# Main.net
KiCad netlist of a schematic drawn in Altium Designer
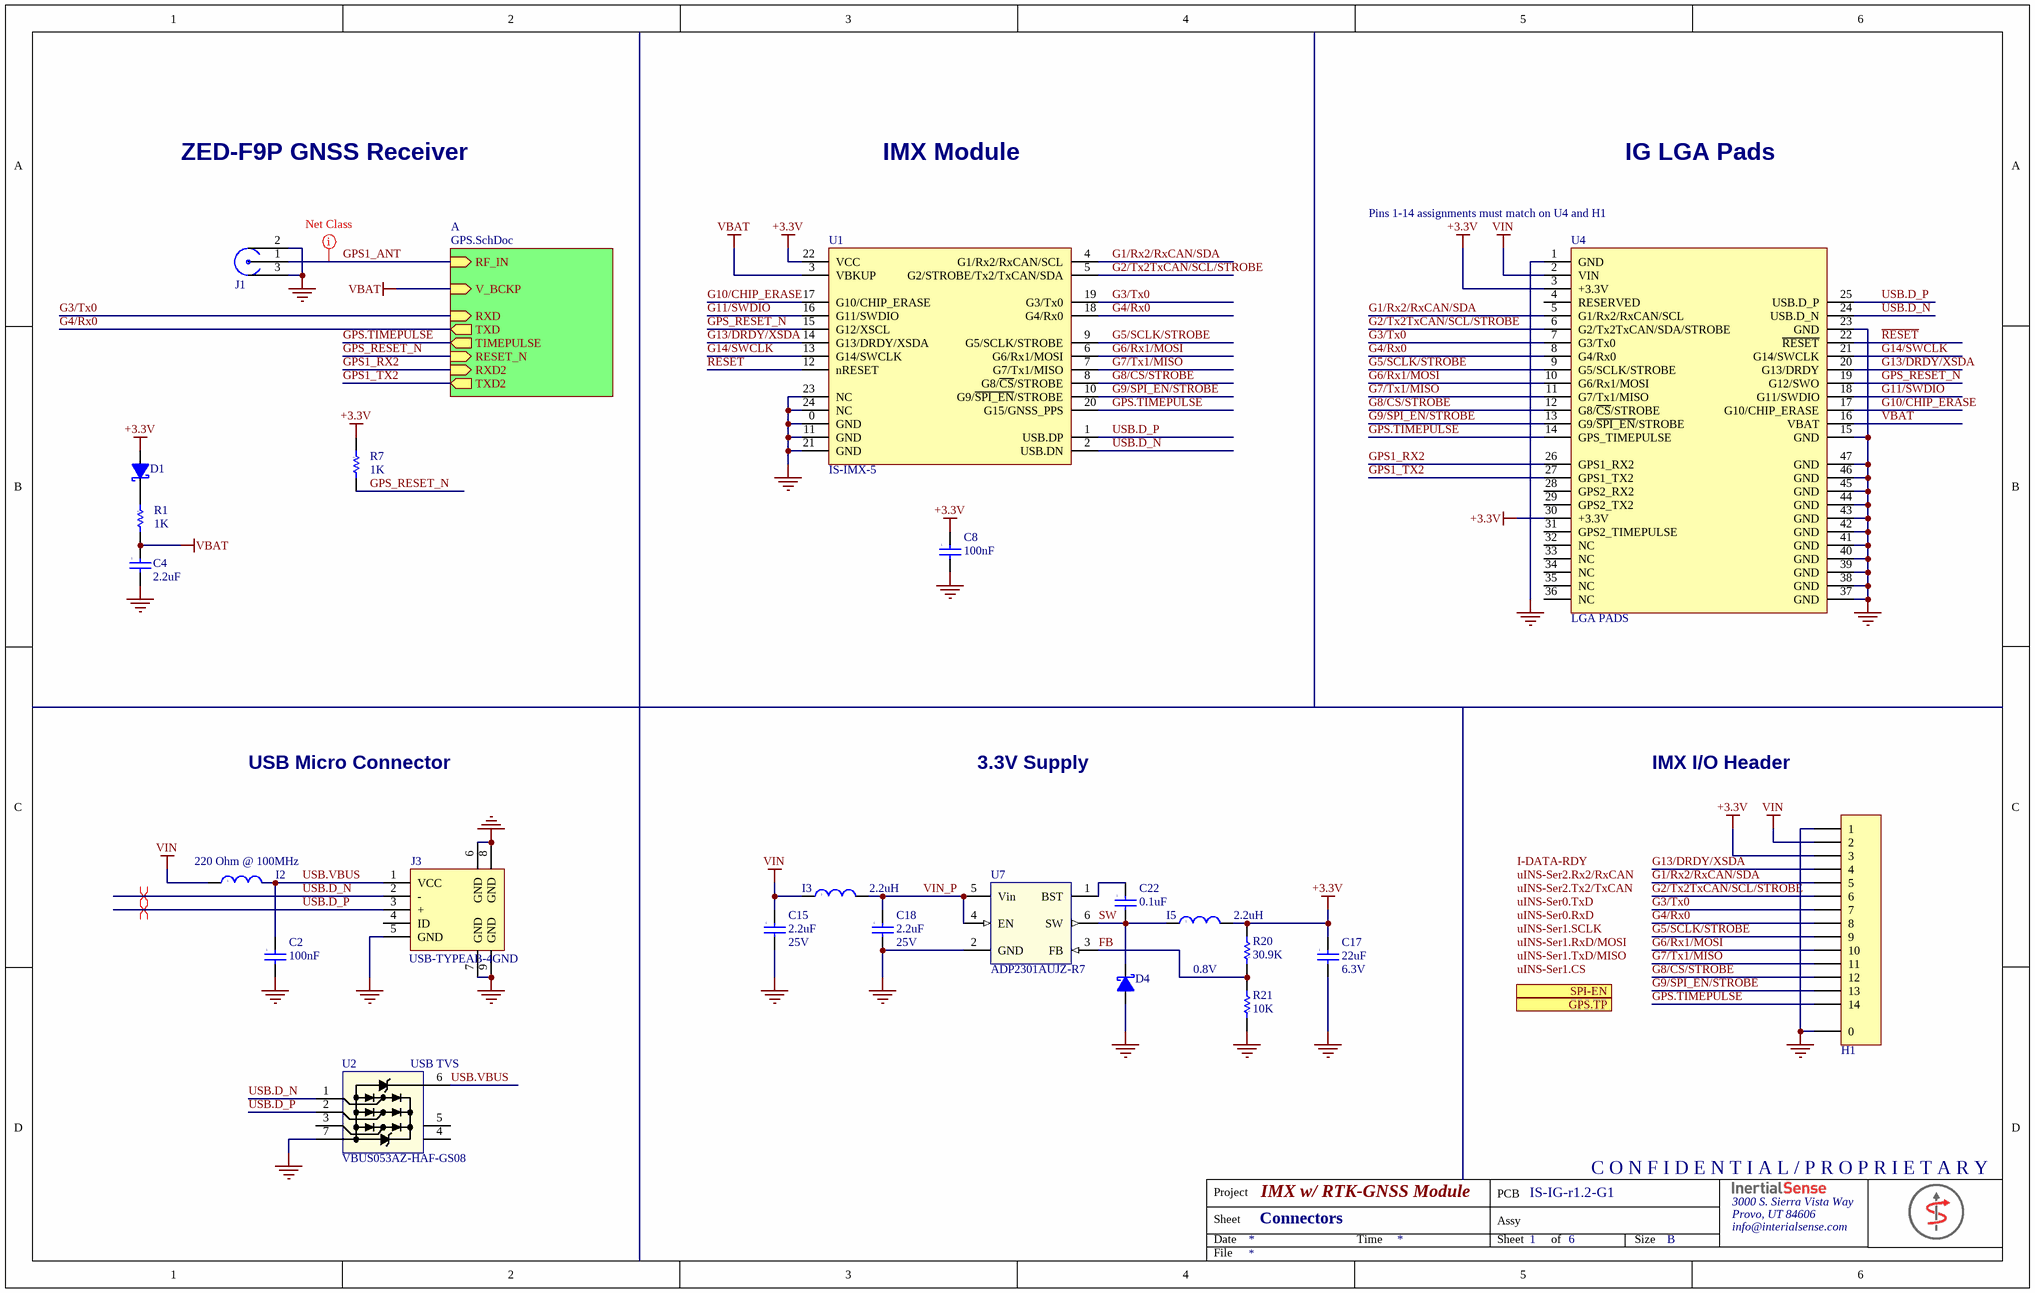
[diagram p0: Main.SchDoc]

(export (version "E")
  (design (tool "Eeschema 10.0.6"))
  (components
    (comp (ref "C2")
      (value "100nF")
      (footprint "0402")
      (description "CAP CER .10UF 50V X7R 10% 0402")
      (fields
        (field (name "MANUFACTURER") "TDK Corporation")
        (field (name "MANUFACTURER PART NUMBER") "C1005X7R1H104K")
        (field (name "PUBLISHER") "Altium Limited")
      )
      (libsource (lib "") (part "Cap_1"))
    )
    (comp (ref "C4")
      (value "2.2uF")
      (footprint "0402")
      (description "0402 2.2 uF 6.3 V ±10% Tolerance X6S Multilayer Ceramic Capacitor")
      (fields
        (field (name "MANUFACTURER") "Murata")
        (field (name "MANUFACTURER PART NUMBER") "GRM155C80J225KE95D")
        (field (name "PUBLISHER") "Altium Limited")
      )
      (libsource (lib "General") (part "Cap"))
    )
    (comp (ref "C8")
      (value "100nF")
      (footprint "0402")
      (description "CAP CER .10UF 50V X7R 10% 0402")
      (fields
        (field (name "MANUFACTURER") "TDK Corporation")
        (field (name "MANUFACTURER PART NUMBER") "C1005X7R1H104K")
        (field (name "PUBLISHER") "Altium Limited")
      )
      (libsource (lib "") (part "Cap_1"))
    )
    (comp (ref "C15")
      (value "2.2uF")
      (footprint "0603")
      (description "CAP CER 2.2UF 25V X6S 0603")
      (fields
        (field (name "MANUFACTURER") "Murata")
        (field (name "MANUFACTURER PART NUMBER") "GRT188C81E225KE13D")
        (field (name "VOLTAGE RATING") "25V")
        (field (name "PUBLISHER") "Altium Limited")
      )
      (libsource (lib "General") (part "Cap"))
    )
    (comp (ref "C17")
      (value "22uF")
      (footprint "0603")
      (description "CAP CER 22UF 6.3V X6S 0603")
      (fields
        (field (name "MANUFACTURER") "Murata")
        (field (name "MANUFACTURER PART NUMBER") "GRM188C80J226ME15D")
        (field (name "VOLTAGE RATING") "6.3V")
        (field (name "PUBLISHER") "Altium Limited")
      )
      (libsource (lib "General") (part "Cap"))
    )
    (comp (ref "C18")
      (value "2.2uF")
      (footprint "0603")
      (description "CAP CER 2.2UF 25V X6S 0603")
      (fields
        (field (name "MANUFACTURER") "Murata")
        (field (name "MANUFACTURER PART NUMBER") "GRT188C81E225KE13D")
        (field (name "VOLTAGE RATING") "25V")
        (field (name "PUBLISHER") "Altium Limited")
      )
      (libsource (lib "General") (part "Cap"))
    )
    (comp (ref "C22")
      (value "0.1uF")
      (footprint "0402")
      (description "CAP CER 0.1UF 50V X7R 0402")
      (fields
        (field (name "MANUFACTURER") "TDK")
        (field (name "MANUFACTURER PART NUMBER") "CGA2B3X7R1H104K050BB")
        (field (name "PUBLISHER") "Altium Limited")
      )
      (libsource (lib "General") (part "Cap"))
    )
    (comp (ref "D1")
      (value "Diode - Schottky")
      (footprint "D0603B")
      (description "DIODE SCHOTTKY 30V 2A 0603")
      (fields
        (field (name "MANUFACTURER") "Vishay")
        (field (name "MANUFACTURER PART NUMBER") "VSKY20301608-G4-08")
      )
      (libsource (lib "General") (part "Diode - Schottky"))
    )
    (comp (ref "D4")
      (value "Diode - Schottky")
      (footprint "D0603B")
      (description "DIODE SCHOTTKY 30V 2A 0603")
      (fields
        (field (name "MANUFACTURER") "Vishay")
        (field (name "MANUFACTURER PART NUMBER") "VSKY20301608-G4-08")
      )
      (libsource (lib "General") (part "Diode - Schottky"))
    )
    (comp (ref "H1")
      (value "Hdr - 14pin - mount")
      (footprint "SM14B-GHS-TB(LF)(SN)")
      (description "Conn Shrouded Header HDR 14 POS 1.25mm Solder ST Top Entry SMD T/R")
      (fields
        (field (name "MANUFACTURER") "JST")
        (field (name "MANUFACTURER PART NUMBER") "SM14B-GHS-TB(LF)(SN)")
      )
      (libsource (lib "Connectors") (part "Hdr - 14pin - mount"))
    )
    (comp (ref "I2")
      (value "220 Ohm @ 100MHz")
      (footprint "I0603")
      (description "FERRITE CHIP 220 OHM 2500MA 0603")
      (fields
        (field (name "MANUFACTURER") "Murata Electronics North America")
        (field (name "MANUFACTURER PART NUMBER") "BLM18SG221TN1D")
      )
      (libsource (lib "General") (part "Inductor"))
    )
    (comp (ref "I3")
      (value "2.2uH")
      (footprint "0806")
      (description "FIXED IND 2.2UH 1.2A 110 MOHM")
      (fields
        (field (name "MANUFACTURER") "TDK")
        (field (name "MANUFACTURER PART NUMBER") "MLP2016H2R2MT0S1")
      )
      (libsource (lib "") (part "Inductor_1"))
    )
    (comp (ref "I5")
      (value "2.2uH")
      (footprint "0806")
      (description "FIXED IND 2.2UH 1.2A 110 MOHM")
      (fields
        (field (name "MANUFACTURER") "TDK")
        (field (name "MANUFACTURER PART NUMBER") "MLP2016H2R2MT0S1")
      )
      (libsource (lib "") (part "Inductor_1"))
    )
    (comp (ref "J1")
      (value "RF - GND x 2")
      (footprint "RF UMC SMD")
      (description "CONN UMC RCPT STR 50 OHM SMD")
      (fields
        (field (name "MANUFACTURER") "Emerson Network Power Connectivity Johnson")
        (field (name "MANUFACTURER PART NUMBER") "128-0711-201")
      )
      (libsource (lib "Connectors") (part "RF - GND x 2"))
    )
    (comp (ref "J3")
      (value "USB-TYPEAB-4GND")
      (footprint "USB Micro AB R/A THR")
      (description "CONN USB AB 4POS")
      (fields
        (field (name "MANUFACTURER") "Amphenol FCI")
        (field (name "MANUFACTURER PART NUMBER") "10118194-0001LF")
      )
      (libsource (lib "Connectors") (part "USB-TYPEAB-4GND"))
    )
    (comp (ref "R1")
      (value "1K")
      (footprint "R0402")
      (description "1 kOhms ±1% 0.063W, 1/16W Chip Resistor 0402 (1005 Metric) Moisture Resistant Thick Film")
      (fields
        (field (name "MANUFACTURER") "Yageo")
        (field (name "MANUFACTURER PART NUMBER") "RC0402FR-071KL")
      )
      (libsource (lib "General") (part "Res"))
    )
    (comp (ref "R7")
      (value "1K")
      (footprint "R0402")
      (description "1 kOhms ±1% 0.063W, 1/16W Chip Resistor 0402 (1005 Metric) Moisture Resistant Thick Film")
      (fields
        (field (name "MANUFACTURER") "Yageo")
        (field (name "MANUFACTURER PART NUMBER") "RC0402FR-071KL")
      )
      (libsource (lib "General") (part "Res"))
    )
    (comp (ref "R20")
      (value "30.9K")
      (footprint "R0402")
      (description "RES TF 30.9K OHM 1% 1/16W 0402")
      (fields
        (field (name "MANUFACTURER") "Stackpole Electronics Inc")
        (field (name "MANUFACTURER PART NUMBER") "RMCF0402FT30K9")
      )
      (libsource (lib "") (part "Res_1"))
    )
    (comp (ref "R21")
      (value "10K")
      (footprint "R0402")
      (description "RES 10.0K OHM 1/16W 1% 0402 SMD")
      (fields
        (field (name "MANUFACTURER") "Yageo")
        (field (name "MANUFACTURER PART NUMBER") "RC0402FR-0710KL")
      )
      (libsource (lib "") (part "Res_1"))
    )
    (comp (ref "U1")
      (value "IMX")
      (footprint "IS-IMX-5.0")
      (description "Inertial Sense IMX")
      (fields
        (field (name "MANUFACTURER") "Inertial Sense")
        (field (name "MANUFACTURER PART NUMBER") "IS-IMX-5")
      )
      (libsource (lib "IS-IMX-5") (part "IS-IMX-5.0"))
    )
    (comp (ref "U2")
      (value "VBUS053")
      (footprint "QFN50P160X160X60-6N")
      (description "ESD SUPPRESS 5.5V 36W 3-Line USB")
      (fields
        (field (name "MANUFACTURER") "Vishay Semiconductors")
        (field (name "MANUFACTURER PART NUMBER") "VBUS053AZ-HAF-GS08")
      )
      (libsource (lib "ICs") (part "VBUS053"))
    )
    (comp (ref "U4")
      (value "LGA PADS")
      (footprint "IG-1.2-G1_LGA")
      (description "IMX multi-frequency RTK-GNSS Module")
      (libsource (lib "Sensors") (part "IG_1.2-G1_LGA"))
    )
    (comp (ref "U7")
      (value "ADP2301")
      (footprint "MO-178-AB")
      (description "IC BUCK ADJ 1.2A 6TSOT")
      (fields
        (field (name "MANUFACTURER") "Analog Devices Inc")
        (field (name "MANUFACTURER PART NUMBER") "ADP2301AUJZ-R7")
      )
      (libsource (lib "ICs") (part "ADP2301"))
    )
  )
  (nets
    (net (code "1") (name "+3.3V") (class "Default")
      (node (ref "C17") (pin "1") (pinfunction "1_1") (pintype "passive"))
      (node (ref "C8") (pin "1") (pinfunction "1_1") (pintype "passive"))
      (node (ref "D1") (pin "A") (pinfunction "A_A") (pintype "passive"))
      (node (ref "H1") (pin "3") (pinfunction "3_3") (pintype "passive"))
      (node (ref "I5") (pin "2") (pinfunction "2_2") (pintype "passive"))
      (node (ref "R20") (pin "2") (pinfunction "2_2") (pintype "passive"))
      (node (ref "R7") (pin "1") (pinfunction "1_1") (pintype "passive"))
      (node (ref "U1") (pin "22") (pinfunction "VCC_22") (pintype "power_in"))
      (node (ref "U4") (pin "3") (pinfunction "+3.3V_3") (pintype "passive"))
      (node (ref "U4") (pin "30") (pinfunction "+3.3V_30") (pintype "passive"))
    )
    (net (code "2") (name "/FB") (class "Default")
      (node (ref "R20") (pin "1") (pinfunction "1_1") (pintype "passive"))
      (node (ref "R21") (pin "2") (pinfunction "2_2") (pintype "passive"))
      (node (ref "U7") (pin "3") (pinfunction "FB_3") (pintype "input"))
    )
    (net (code "3") (name "/G1{slash}Rx2{slash}RxCAN{slash}SDA") (class "Default")
      (node (ref "H1") (pin "5") (pinfunction "5_5") (pintype "passive"))
      (node (ref "U1") (pin "4") (pinfunction "G1/Rx2/RxCAN/SCL_4") (pintype "passive"))
      (node (ref "U4") (pin "5") (pinfunction "G1/Rx2/RxCAN/SCL_5") (pintype "passive"))
    )
    (net (code "4") (name "/G2{slash}Tx2TxCAN{slash}SCL{slash}STROBE") (class "Default")
      (node (ref "H1") (pin "6") (pinfunction "6_6") (pintype "passive"))
      (node (ref "U1") (pin "5") (pinfunction "G2/STROBE/Tx2/TxCAN/SDA_5") (pintype "passive"))
      (node (ref "U4") (pin "6") (pinfunction "G2/Tx2TxCAN/SDA/STROBE_6") (pintype "passive"))
    )
    (net (code "5") (name "/G3{slash}Tx0") (class "Default")
      (node (ref "H1") (pin "7") (pinfunction "7_7") (pintype "passive"))
      (node (ref "U1") (pin "19") (pinfunction "G3/Tx0_19") (pintype "passive"))
      (node (ref "U4") (pin "7") (pinfunction "G3/Tx0_7") (pintype "passive"))
    )
    (net (code "6") (name "/G4{slash}Rx0") (class "Default")
      (node (ref "H1") (pin "8") (pinfunction "8_8") (pintype "passive"))
      (node (ref "U1") (pin "18") (pinfunction "G4/Rx0_18") (pintype "passive"))
      (node (ref "U4") (pin "8") (pinfunction "G4/Rx0_8") (pintype "passive"))
    )
    (net (code "7") (name "/G5{slash}SCLK{slash}STROBE") (class "Default")
      (node (ref "H1") (pin "9") (pinfunction "9_9") (pintype "passive"))
      (node (ref "U1") (pin "9") (pinfunction "G5/SCLK/STROBE_9") (pintype "passive"))
      (node (ref "U4") (pin "9") (pinfunction "G5/SCLK/STROBE_9") (pintype "passive"))
    )
    (net (code "8") (name "/G6{slash}Rx1{slash}MOSI") (class "Default")
      (node (ref "H1") (pin "10") (pinfunction "10_10") (pintype "passive"))
      (node (ref "U1") (pin "6") (pinfunction "G6/Rx1/MOSI_6") (pintype "passive"))
      (node (ref "U4") (pin "10") (pinfunction "G6/Rx1/MOSI_10") (pintype "passive"))
    )
    (net (code "9") (name "/G7{slash}Tx1{slash}MISO") (class "Default")
      (node (ref "H1") (pin "11") (pinfunction "11_11") (pintype "passive"))
      (node (ref "U1") (pin "7") (pinfunction "G7/Tx1/MISO_7") (pintype "passive"))
      (node (ref "U4") (pin "11") (pinfunction "G7/Tx1/MISO_11") (pintype "passive"))
    )
    (net (code "10") (name "/G8{slash}~{CS}{slash}STROBE") (class "Default")
      (node (ref "H1") (pin "12") (pinfunction "12_12") (pintype "passive"))
      (node (ref "U1") (pin "8") (pinfunction "G8/~{CS}/STROBE_8") (pintype "passive"))
      (node (ref "U4") (pin "12") (pinfunction "G8/~{CS}/STROBE_12") (pintype "passive"))
    )
    (net (code "11") (name "/G9{slash}~{SPI_EN}{slash}STROBE") (class "Default")
      (node (ref "H1") (pin "13") (pinfunction "13_13") (pintype "passive"))
      (node (ref "U1") (pin "10") (pinfunction "G9/~{SPI_EN}/STROBE_10") (pintype "passive"))
      (node (ref "U4") (pin "13") (pinfunction "G9/~{SPI_EN}/STROBE_13") (pintype "passive"))
    )
    (net (code "12") (name "/G10{slash}CHIP_ERASE") (class "Default")
      (node (ref "U1") (pin "17") (pinfunction "G10/CHIP_ERASE_17") (pintype "passive"))
      (node (ref "U4") (pin "17") (pinfunction "G10/CHIP_ERASE_17") (pintype "passive"))
    )
    (net (code "13") (name "/G11{slash}SWDIO") (class "Default")
      (node (ref "U1") (pin "16") (pinfunction "G11/SWDIO_16") (pintype "passive"))
      (node (ref "U4") (pin "18") (pinfunction "G11/SWDIO_18") (pintype "passive"))
    )
    (net (code "14") (name "/G13{slash}DRDY{slash}XSDA") (class "Default")
      (node (ref "H1") (pin "4") (pinfunction "4_4") (pintype "passive"))
      (node (ref "U1") (pin "14") (pinfunction "G13/DRDY/XSDA_14") (pintype "passive"))
      (node (ref "U4") (pin "20") (pinfunction "G13/DRDY_20") (pintype "passive"))
    )
    (net (code "15") (name "/G14{slash}SWCLK") (class "Default")
      (node (ref "U1") (pin "13") (pinfunction "G14/SWCLK_13") (pintype "passive"))
      (node (ref "U4") (pin "21") (pinfunction "G14/SWCLK_21") (pintype "passive"))
    )
    (net (code "16") (name "/GPS.TIMEPULSE") (class "Default")
      (node (ref "H1") (pin "14") (pinfunction "14_14") (pintype "passive"))
      (node (ref "U1") (pin "20") (pinfunction "G15/GNSS_PPS_20") (pintype "passive"))
      (node (ref "U4") (pin "14") (pinfunction "GPS_TIMEPULSE_14") (pintype "passive"))
    )
    (net (code "18") (name "/GPS1_ANT") (class "Default")
      (node (ref "J1") (pin "1") (pinfunction "1_1") (pintype "passive"))
    )
    (net (code "19") (name "/GPS1_RX2") (class "Default")
      (node (ref "U4") (pin "26") (pinfunction "GPS1_RX2_26") (pintype "passive"))
    )
    (net (code "20") (name "/GPS1_TX2") (class "Default")
      (node (ref "U4") (pin "27") (pinfunction "GPS1_TX2_27") (pintype "passive"))
    )
    (net (code "21") (name "/GPS_RESET_N") (class "Default")
      (node (ref "R7") (pin "2") (pinfunction "2_2") (pintype "passive"))
      (node (ref "U1") (pin "15") (pinfunction "G12/XSCL_15") (pintype "passive"))
      (node (ref "U4") (pin "19") (pinfunction "G12/SWO_19") (pintype "passive"))
    )
    (net (code "23") (name "/RESET") (class "Default")
      (node (ref "U1") (pin "12") (pinfunction "nRESET_12") (pintype "passive"))
      (node (ref "U4") (pin "22") (pinfunction "~{RESET}_22") (pintype "passive"))
    )
    (net (code "25") (name "/SW") (class "Default")
      (node (ref "C22") (pin "2") (pinfunction "2_2") (pintype "passive"))
      (node (ref "D4") (pin "C") (pinfunction "C_C") (pintype "passive"))
      (node (ref "I5") (pin "1") (pinfunction "1_1") (pintype "passive"))
      (node (ref "U7") (pin "6") (pinfunction "SW_6") (pintype "output"))
    )
    (net (code "26") (name "/USB.D_N") (class "Default")
      (node (ref "J3") (pin "2") (pinfunction "-_2") (pintype "passive"))
      (node (ref "U1") (pin "2") (pinfunction "USB.DN_2") (pintype "passive"))
      (node (ref "U2") (pin "1") (pintype "passive"))
      (node (ref "U4") (pin "24") (pinfunction "USB.D_N_24") (pintype "passive"))
    )
    (net (code "27") (name "/USB.D_P") (class "Default")
      (node (ref "J3") (pin "3") (pinfunction "+_3") (pintype "passive"))
      (node (ref "U1") (pin "1") (pinfunction "USB.DP_1") (pintype "passive"))
      (node (ref "U2") (pin "2") (pintype "passive"))
      (node (ref "U4") (pin "25") (pinfunction "USB.D_P_25") (pintype "passive"))
    )
    (net (code "28") (name "/USB.VBUS") (class "Default")
      (node (ref "C2") (pin "1") (pinfunction "1_1") (pintype "passive"))
      (node (ref "I2") (pin "2") (pinfunction "2_2") (pintype "passive"))
      (node (ref "J3") (pin "1") (pinfunction "VCC_1") (pintype "passive"))
      (node (ref "U2") (pin "6") (pintype "passive"))
    )
    (net (code "29") (name "/VIN_P") (class "Default")
      (node (ref "C18") (pin "1") (pinfunction "1_1") (pintype "passive"))
      (node (ref "I3") (pin "2") (pinfunction "2_2") (pintype "passive"))
      (node (ref "U7") (pin "4") (pinfunction "EN_4") (pintype "input"))
      (node (ref "U7") (pin "5") (pinfunction "Vin_5") (pintype "power_in"))
    )
    (net (code "38") (name "GND") (class "Default")
      (node (ref "C15") (pin "2") (pinfunction "2_2") (pintype "passive"))
      (node (ref "C17") (pin "2") (pinfunction "2_2") (pintype "passive"))
      (node (ref "C18") (pin "2") (pinfunction "2_2") (pintype "passive"))
      (node (ref "C2") (pin "2") (pinfunction "2_2") (pintype "passive"))
      (node (ref "C4") (pin "2") (pinfunction "2_2") (pintype "passive"))
      (node (ref "C8") (pin "2") (pinfunction "2_2") (pintype "passive"))
      (node (ref "D4") (pin "A") (pinfunction "A_A") (pintype "passive"))
      (node (ref "H1") (pin "0") (pinfunction "0_0") (pintype "passive"))
      (node (ref "H1") (pin "1") (pinfunction "1_1") (pintype "passive"))
      (node (ref "J1") (pin "2") (pinfunction "2_2") (pintype "passive"))
      (node (ref "J1") (pin "3") (pinfunction "3_3") (pintype "passive"))
      (node (ref "J3") (pin "5") (pinfunction "GND_5") (pintype "passive"))
      (node (ref "J3") (pin "6") (pinfunction "GND_6") (pintype "passive"))
      (node (ref "J3") (pin "7") (pinfunction "GND_7") (pintype "passive"))
      (node (ref "J3") (pin "8") (pinfunction "GND_8") (pintype "passive"))
      (node (ref "J3") (pin "9") (pinfunction "GND_9") (pintype "passive"))
      (node (ref "R21") (pin "1") (pinfunction "1_1") (pintype "passive"))
      (node (ref "U1") (pin "0") (pinfunction "GND_0") (pintype "power_in"))
      (node (ref "U1") (pin "11") (pinfunction "GND_11") (pintype "power_in"))
      (node (ref "U1") (pin "21") (pinfunction "GND_21") (pintype "power_in"))
      (node (ref "U1") (pin "23") (pinfunction "NC_23") (pintype "power_in"))
      (node (ref "U1") (pin "24") (pinfunction "NC_24") (pintype "power_in"))
      (node (ref "U2") (pin "7") (pintype "passive"))
      (node (ref "U4") (pin "1") (pinfunction "GND_1") (pintype "passive"))
      (node (ref "U4") (pin "15") (pinfunction "GND_15") (pintype "passive"))
      (node (ref "U4") (pin "23") (pinfunction "GND_23") (pintype "passive"))
      (node (ref "U4") (pin "37") (pinfunction "GND_37") (pintype "passive"))
      (node (ref "U4") (pin "38") (pinfunction "GND_38") (pintype "passive"))
      (node (ref "U4") (pin "39") (pinfunction "GND_39") (pintype "passive"))
      (node (ref "U4") (pin "40") (pinfunction "GND_40") (pintype "passive"))
      (node (ref "U4") (pin "41") (pinfunction "GND_41") (pintype "passive"))
      (node (ref "U4") (pin "42") (pinfunction "GND_42") (pintype "passive"))
      (node (ref "U4") (pin "43") (pinfunction "GND_43") (pintype "passive"))
      (node (ref "U4") (pin "44") (pinfunction "GND_44") (pintype "passive"))
      (node (ref "U4") (pin "45") (pinfunction "GND_45") (pintype "passive"))
      (node (ref "U4") (pin "46") (pinfunction "GND_46") (pintype "passive"))
      (node (ref "U4") (pin "47") (pinfunction "GND_47") (pintype "passive"))
      (node (ref "U7") (pin "2") (pinfunction "GND_2") (pintype "power_in"))
    )
    (net (code "39") (name "Net-(D1-PadC)") (class "Default")
      (node (ref "D1") (pin "C") (pinfunction "C_C") (pintype "passive"))
      (node (ref "R1") (pin "1") (pinfunction "1_1") (pintype "passive"))
    )
    (net (code "40") (name "Net-(U7-BST)") (class "Default")
      (node (ref "C22") (pin "1") (pinfunction "1_1") (pintype "passive"))
      (node (ref "U7") (pin "1") (pinfunction "BST_1") (pintype "passive"))
    )
    (net (code "41") (name "VBAT") (class "Default")
      (node (ref "C4") (pin "1") (pinfunction "1_1") (pintype "passive"))
      (node (ref "R1") (pin "2") (pinfunction "2_2") (pintype "passive"))
      (node (ref "U1") (pin "3") (pinfunction "VBKUP_3") (pintype "passive"))
      (node (ref "U4") (pin "16") (pinfunction "VBAT_16") (pintype "passive"))
    )
    (net (code "42") (name "VIN") (class "Default")
      (node (ref "C15") (pin "1") (pinfunction "1_1") (pintype "passive"))
      (node (ref "H1") (pin "2") (pinfunction "2_2") (pintype "passive"))
      (node (ref "I2") (pin "1") (pinfunction "1_1") (pintype "passive"))
      (node (ref "I3") (pin "1") (pinfunction "1_1") (pintype "passive"))
      (node (ref "U4") (pin "2") (pinfunction "VIN_2") (pintype "passive"))
    )
    (net (code "43") (name "unconnected-(J3-ID-Pad4)") (class "Default")
      (node (ref "J3") (pin "4") (pinfunction "ID_4") (pintype "passive"))
    )
    (net (code "44") (name "unconnected-(U2-Pad3)") (class "Default")
      (node (ref "U2") (pin "3") (pintype "passive"))
    )
    (net (code "45") (name "unconnected-(U2-nc-Pad4)") (class "Default")
      (node (ref "U2") (pin "4") (pinfunction "nc_4") (pintype "passive"))
    )
    (net (code "46") (name "unconnected-(U2-nc-Pad5)") (class "Default")
      (node (ref "U2") (pin "5") (pinfunction "nc_5") (pintype "passive"))
    )
    (net (code "47") (name "unconnected-(U4-GPS2_RX2-Pad28)") (class "Default")
      (node (ref "U4") (pin "28") (pinfunction "GPS2_RX2_28") (pintype "passive"))
    )
    (net (code "48") (name "unconnected-(U4-GPS2_TIMEPULSE-Pad31)") (class "Default")
      (node (ref "U4") (pin "31") (pinfunction "GPS2_TIMEPULSE_31") (pintype "passive"))
    )
    (net (code "49") (name "unconnected-(U4-GPS2_TX2-Pad29)") (class "Default")
      (node (ref "U4") (pin "29") (pinfunction "GPS2_TX2_29") (pintype "passive"))
    )
    (net (code "50") (name "unconnected-(U4-NC-Pad32)") (class "Default")
      (node (ref "U4") (pin "32") (pinfunction "NC_32") (pintype "passive"))
    )
    (net (code "51") (name "unconnected-(U4-NC-Pad33)") (class "Default")
      (node (ref "U4") (pin "33") (pinfunction "NC_33") (pintype "passive"))
    )
    (net (code "52") (name "unconnected-(U4-NC-Pad34)") (class "Default")
      (node (ref "U4") (pin "34") (pinfunction "NC_34") (pintype "passive"))
    )
    (net (code "53") (name "unconnected-(U4-NC-Pad35)") (class "Default")
      (node (ref "U4") (pin "35") (pinfunction "NC_35") (pintype "passive"))
    )
    (net (code "54") (name "unconnected-(U4-NC-Pad36)") (class "Default")
      (node (ref "U4") (pin "36") (pinfunction "NC_36") (pintype "passive"))
    )
    (net (code "55") (name "unconnected-(U4-RESERVED-Pad4)") (class "Default")
      (node (ref "U4") (pin "4") (pinfunction "RESERVED_4") (pintype "passive"))
    )
  )
)
